# FMU_Power_FMU_REV_2A.net
KiCad netlist of a schematic drawn in Altium Designer
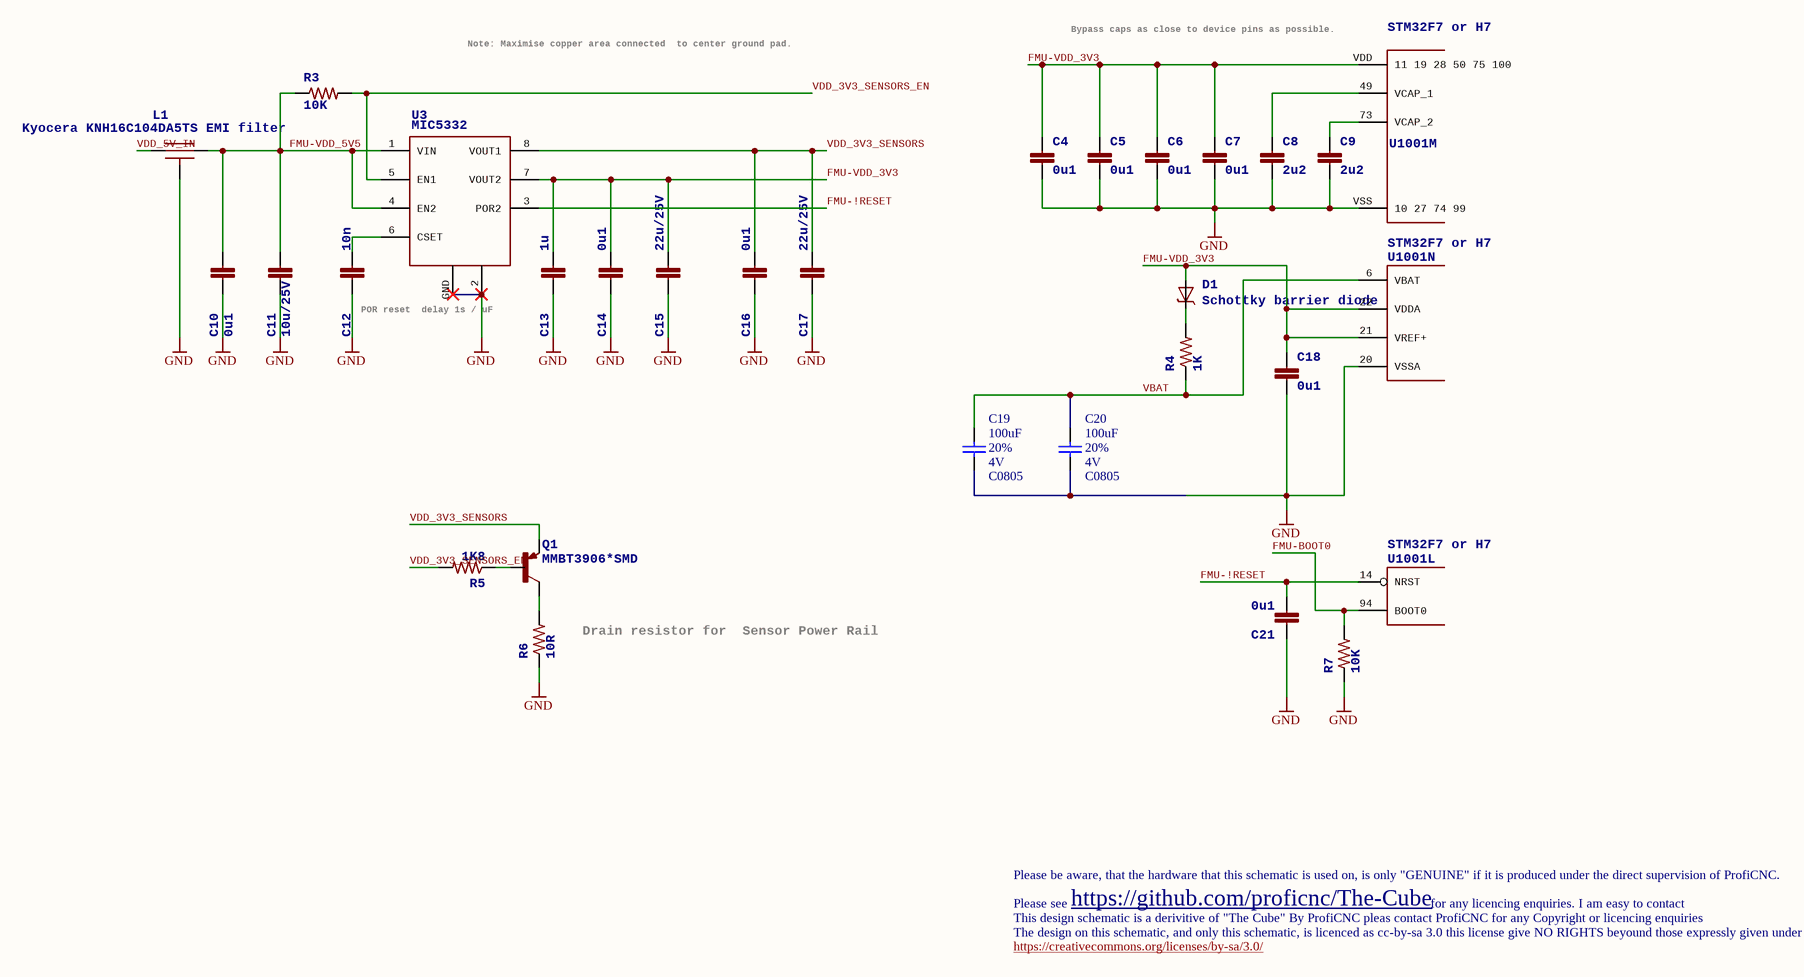
[diagram p0: FMU_Power_FMU_REV_2A.SchDoc]

(export (version "E")
  (design (tool "Eeschema 10.0.6"))
  (components
    (comp (ref "C4")
      (value "0u1")
      (footprint "0402-CAP")
      (description "CAP CER 0.1UF 16V Y5V 0402")
      (libsource (lib "pixhawk2") (part "CAP0402"))
    )
    (comp (ref "C5")
      (value "0u1")
      (footprint "0402-CAP")
      (description "CAP CER 0.1UF 16V Y5V 0402")
      (libsource (lib "pixhawk2") (part "CAP0402"))
    )
    (comp (ref "C6")
      (value "0u1")
      (footprint "0402-CAP")
      (description "CAP CER 0.1UF 16V Y5V 0402")
      (libsource (lib "pixhawk2") (part "CAP0402"))
    )
    (comp (ref "C7")
      (value "0u1")
      (footprint "0402-CAP")
      (description "CAP CER 0.1UF 16V Y5V 0402")
      (libsource (lib "pixhawk2") (part "CAP0402"))
    )
    (comp (ref "C8")
      (value "2u2")
      (footprint "0603-CAP")
      (description "CAP CER 2.2UF 16V 10% X6S 0603")
      (libsource (lib "pixhawk2") (part "CAP0603"))
    )
    (comp (ref "C9")
      (value "2u2")
      (footprint "0603-CAP")
      (description "CAP CER 2.2UF 16V 10% X6S 0603")
      (libsource (lib "pixhawk2") (part "CAP0603"))
    )
    (comp (ref "C10")
      (value "0u1")
      (footprint "0402-CAP")
      (description "CAP CER 0.1UF 16V Y5V 0402")
      (libsource (lib "pixhawk2") (part "CAP0402"))
    )
    (comp (ref "C11")
      (value "10u/25V")
      (footprint "0805-CAP")
      (description "CAP CER 10UF 25V 10% X5R 0805")
      (libsource (lib "pixhawk2") (part "CAP0805"))
    )
    (comp (ref "C12")
      (value "10n")
      (footprint "0402-CAP")
      (description "CAP CER 10000PF 16V 10% X7R 0402")
      (libsource (lib "") (part "CAP0402_1"))
    )
    (comp (ref "C13")
      (value "1u")
      (footprint "0603-CAP")
      (description "CAP CER 1UF 16V Y5V 0603")
      (libsource (lib "pixhawk2") (part "CAP0603"))
    )
    (comp (ref "C14")
      (value "0u1")
      (footprint "0402-CAP")
      (description "CAP CER 0.1UF 16V Y5V 0402")
      (libsource (lib "pixhawk2") (part "CAP0402"))
    )
    (comp (ref "C15")
      (value "22u/25V")
      (footprint "0805-CAP")
      (description "CAP CER 22UF 25V 20% X5R 0805")
      (libsource (lib "pixhawk2") (part "CAP0805"))
    )
    (comp (ref "C16")
      (value "0u1")
      (footprint "0402-CAP")
      (description "CAP CER 0.1UF 16V Y5V 0402")
      (libsource (lib "pixhawk2") (part "CAP0402"))
    )
    (comp (ref "C17")
      (value "22u/25V")
      (footprint "0805-CAP")
      (description "CAP CER 22UF 25V 20% X5R 0805")
      (libsource (lib "pixhawk2") (part "CAP0805"))
    )
    (comp (ref "C18")
      (value "0u1")
      (footprint "0402-CAP")
      (description "CAP CER 0.1UF 16V Y5V 0402")
      (libsource (lib "pixhawk2") (part "CAP0402"))
    )
    (comp (ref "C19")
      (value "100uF")
      (footprint "C0805")
      (fields
        (field (name "TOLERANCE") "20%")
        (field (name "VOLTAGE") "4V")
        (field (name "Comment") "GRM21BR60G107ME15L")
      )
      (libsource (lib "3DR") (part "Capacitor"))
    )
    (comp (ref "C20")
      (value "100uF")
      (footprint "C0805")
      (fields
        (field (name "TOLERANCE") "20%")
        (field (name "VOLTAGE") "4V")
        (field (name "Comment") "GRM21BR60G107ME15L")
      )
      (libsource (lib "3DR") (part "Capacitor"))
    )
    (comp (ref "C21")
      (value "0u1")
      (footprint "0402-CAP")
      (description "CAP CER 0.1UF 16V Y5V 0402")
      (libsource (lib "") (part "CAP0402_2"))
    )
    (comp (ref "D1")
      (value "Schottky barrier diode")
      (footprint "SOD323")
      (description "DIODE SCHOTTKY 30V 0.03A SOD323")
      (libsource (lib "pixhawk2") (part "DIODE-SCHOTTKY_SOD323"))
    )
    (comp (ref "L1")
      (value "Kyocera KNH16C104DA5TS EMI filter")
      (footprint "KYOCERA-KNH16-DA")
      (description "FILTER CAP 0.1UF 2A 25V 0603")
      (libsource (lib "pixhawk2") (part "KNH16C104DA5TS"))
    )
    (comp (ref "Q1")
      (value "MMBT3906*SMD")
      (footprint "SOT23-BEC")
      (description "TRANSISTOR SWITCHING PNP SOT-23")
      (libsource (lib "transistor-pnp") (part "MMBT3906*SMD"))
    )
    (comp (ref "R3")
      (value "10K")
      (footprint "0402-RES")
      (description "RES 10K OHM 1/16W 1% 0402 SMD")
      (libsource (lib "pixhawk2") (part "RESISTOR0402-RES"))
    )
    (comp (ref "R4")
      (value "1K")
      (footprint "0402-RES")
      (description "RES 1K OHM 1/16W 1% 0402")
      (libsource (lib "pixhawk2") (part "RESISTOR0402-RES"))
    )
    (comp (ref "R5")
      (value "1K8")
      (footprint "0402-RES")
      (description "RES 1.8K OHM 1/16W 1% 0402")
      (libsource (lib "pixhawk2") (part "RESISTOR0402-RES"))
    )
    (comp (ref "R6")
      (value "10R")
      (footprint "0603-RES")
      (description "RES 10 OHM 1/10W 5% 0603")
      (libsource (lib "pixhawk2") (part "RESISTOR0603-RES"))
    )
    (comp (ref "R7")
      (value "10K")
      (footprint "0402-RES")
      (description "RES 10K OHM 1/16W 1% 0402 SMD")
      (libsource (lib "pixhawk2") (part "RESISTOR0402-RES"))
    )
    (comp (ref "U3")
      (value "MIC5332")
      (footprint "MLF-8-EPAD")
      (description "IC REG LDO 3.3V 0.3A 8TMLF")
      (libsource (lib "pixhawk2") (part "MIC5332"))
    )
    (comp (ref "U1001")
      (value "STM32F7 or H7")
      (footprint "TQFP100")
      (description "REV 3 Silicon or later IC MCU ARM 2MB FLASH 100LQFP")
      (libsource (lib "pixhawk2") (part "STM32F4X7VX"))
    )
  )
  (nets
    (net (code "1") (name "/FMU-!RESET") (class "Default")
      (node (ref "C21") (pin "P$2") (pinfunction "2_P$2") (pintype "passive"))
      (node (ref "U1001") (pin "14") (pinfunction "NRST_14") (pintype "passive"))
      (node (ref "U3") (pin "3") (pinfunction "POR2_3") (pintype "passive"))
    )
    (net (code "2") (name "/FMU-BOOT0") (class "Default")
      (node (ref "R7") (pin "P$2") (pinfunction "2_P$2") (pintype "passive"))
      (node (ref "U1001") (pin "94") (pinfunction "BOOT0_94") (pintype "passive"))
    )
    (net (code "3") (name "/FMU-VDD_3V3") (class "Default")
      (node (ref "C13") (pin "P$1") (pinfunction "1_P$1") (pintype "passive"))
      (node (ref "C14") (pin "P$1") (pinfunction "1_P$1") (pintype "passive"))
      (node (ref "C15") (pin "P$1") (pinfunction "1_P$1") (pintype "passive"))
      (node (ref "C18") (pin "P$1") (pinfunction "1_P$1") (pintype "passive"))
      (node (ref "C4") (pin "P$1") (pinfunction "1_P$1") (pintype "passive"))
      (node (ref "C5") (pin "P$1") (pinfunction "1_P$1") (pintype "passive"))
      (node (ref "C6") (pin "P$1") (pinfunction "1_P$1") (pintype "passive"))
      (node (ref "C7") (pin "P$1") (pinfunction "1_P$1") (pintype "passive"))
      (node (ref "D1") (pin "A") (pinfunction "A_A") (pintype "passive"))
      (node (ref "U1001") (pin "21") (pinfunction "VREF+_21") (pintype "passive"))
      (node (ref "U1001") (pin "22") (pinfunction "VDDA_22") (pintype "power_in"))
      (node (ref "U1001") (pin "VDD") (pinfunction "11_19_28_50_75_100_VDD") (pintype "power_in"))
      (node (ref "U3") (pin "7") (pinfunction "VOUT2_7") (pintype "passive"))
    )
    (net (code "4") (name "/FMU-VDD_5V5") (class "Default")
      (node (ref "C10") (pin "P$1") (pinfunction "1_P$1") (pintype "passive"))
      (node (ref "C11") (pin "P$1") (pinfunction "1_P$1") (pintype "passive"))
      (node (ref "L1") (pin "P$2") (pinfunction "P$2_P$2") (pintype "passive"))
      (node (ref "R3") (pin "P$1") (pinfunction "1_P$1") (pintype "passive"))
      (node (ref "U3") (pin "1") (pinfunction "VIN_1") (pintype "passive"))
      (node (ref "U3") (pin "4") (pinfunction "EN2_4") (pintype "passive"))
    )
    (net (code "5") (name "/VBAT") (class "Default")
      (node (ref "C19") (pin "2") (pinfunction "2_2") (pintype "passive"))
      (node (ref "C20") (pin "2") (pinfunction "2_2") (pintype "passive"))
      (node (ref "R4") (pin "P$1") (pinfunction "1_P$1") (pintype "passive"))
      (node (ref "U1001") (pin "6") (pinfunction "VBAT_6") (pintype "power_in"))
    )
    (net (code "6") (name "/VDD_3V3_SENSORS") (class "Default")
      (node (ref "C16") (pin "P$1") (pinfunction "1_P$1") (pintype "passive"))
      (node (ref "C17") (pin "P$1") (pinfunction "1_P$1") (pintype "passive"))
      (node (ref "Q1") (pin "E") (pinfunction "E_E") (pintype "passive"))
      (node (ref "U3") (pin "8") (pinfunction "VOUT1_8") (pintype "passive"))
    )
    (net (code "7") (name "/VDD_3V3_SENSORS_EN") (class "Default")
      (node (ref "R3") (pin "P$2") (pinfunction "2_P$2") (pintype "passive"))
      (node (ref "R5") (pin "P$2") (pinfunction "2_P$2") (pintype "passive"))
      (node (ref "U3") (pin "5") (pinfunction "EN1_5") (pintype "passive"))
    )
    (net (code "8") (name "/VDD_5V_IN") (class "Default")
      (node (ref "L1") (pin "P$1") (pinfunction "P$1_P$1") (pintype "passive"))
    )
    (net (code "9") (name "GND") (class "Default")
      (node (ref "C10") (pin "P$2") (pinfunction "2_P$2") (pintype "passive"))
      (node (ref "C11") (pin "P$2") (pinfunction "2_P$2") (pintype "passive"))
      (node (ref "C12") (pin "P$1") (pinfunction "1_P$1") (pintype "passive"))
      (node (ref "C13") (pin "P$2") (pinfunction "2_P$2") (pintype "passive"))
      (node (ref "C14") (pin "P$2") (pinfunction "2_P$2") (pintype "passive"))
      (node (ref "C15") (pin "P$2") (pinfunction "2_P$2") (pintype "passive"))
      (node (ref "C16") (pin "P$2") (pinfunction "2_P$2") (pintype "passive"))
      (node (ref "C17") (pin "P$2") (pinfunction "2_P$2") (pintype "passive"))
      (node (ref "C18") (pin "P$2") (pinfunction "2_P$2") (pintype "passive"))
      (node (ref "C19") (pin "1") (pinfunction "1_1") (pintype "passive"))
      (node (ref "C20") (pin "1") (pinfunction "1_1") (pintype "passive"))
      (node (ref "C21") (pin "P$1") (pinfunction "1_P$1") (pintype "passive"))
      (node (ref "C4") (pin "P$2") (pinfunction "2_P$2") (pintype "passive"))
      (node (ref "C5") (pin "P$2") (pinfunction "2_P$2") (pintype "passive"))
      (node (ref "C6") (pin "P$2") (pinfunction "2_P$2") (pintype "passive"))
      (node (ref "C7") (pin "P$2") (pinfunction "2_P$2") (pintype "passive"))
      (node (ref "C8") (pin "P$2") (pinfunction "2_P$2") (pintype "passive"))
      (node (ref "C9") (pin "P$2") (pinfunction "2_P$2") (pintype "passive"))
      (node (ref "L1") (pin "GND") (pinfunction "GND_GND") (pintype "passive"))
      (node (ref "R6") (pin "1") (pinfunction "1_1") (pintype "passive"))
      (node (ref "R7") (pin "P$1") (pinfunction "1_P$1") (pintype "passive"))
      (node (ref "U1001") (pin "20") (pinfunction "VSSA_20") (pintype "power_in"))
      (node (ref "U1001") (pin "VSS") (pinfunction "10_27_74_99_VSS") (pintype "power_in"))
      (node (ref "U3") (pin "2") (pinfunction "GND_2") (pintype "power_in"))
      (node (ref "U3") (pin "GND") (pinfunction "GND_GND") (pintype "power_in"))
    )
    (net (code "10") (name "Net-(C8-1)") (class "Default")
      (node (ref "C8") (pin "P$1") (pinfunction "1_P$1") (pintype "passive"))
      (node (ref "U1001") (pin "49") (pinfunction "VCAP_1_49") (pintype "power_in"))
    )
    (net (code "11") (name "Net-(C9-1)") (class "Default")
      (node (ref "C9") (pin "P$1") (pinfunction "1_P$1") (pintype "passive"))
      (node (ref "U1001") (pin "73") (pinfunction "VCAP_2_73") (pintype "power_in"))
    )
    (net (code "12") (name "Net-(C12-2)") (class "Default")
      (node (ref "C12") (pin "P$2") (pinfunction "2_P$2") (pintype "passive"))
      (node (ref "U3") (pin "6") (pinfunction "CSET_6") (pintype "passive"))
    )
    (net (code "13") (name "Net-(Q1-PadC)") (class "Default")
      (node (ref "Q1") (pin "C") (pinfunction "C_C") (pintype "passive"))
      (node (ref "R6") (pin "2") (pinfunction "2_2") (pintype "passive"))
    )
    (net (code "14") (name "Net-(R4-2)") (class "Default")
      (node (ref "D1") (pin "C") (pinfunction "C_C") (pintype "passive"))
      (node (ref "R4") (pin "P$2") (pinfunction "2_P$2") (pintype "passive"))
    )
    (net (code "15") (name "Net-(R5-1)") (class "Default")
      (node (ref "Q1") (pin "B") (pinfunction "B_B") (pintype "passive"))
      (node (ref "R5") (pin "P$1") (pinfunction "1_P$1") (pintype "passive"))
    )
  )
)
